# Teensy3_based_M_M_board_V4.net
KiCad netlist of a schematic drawn in EAGLE
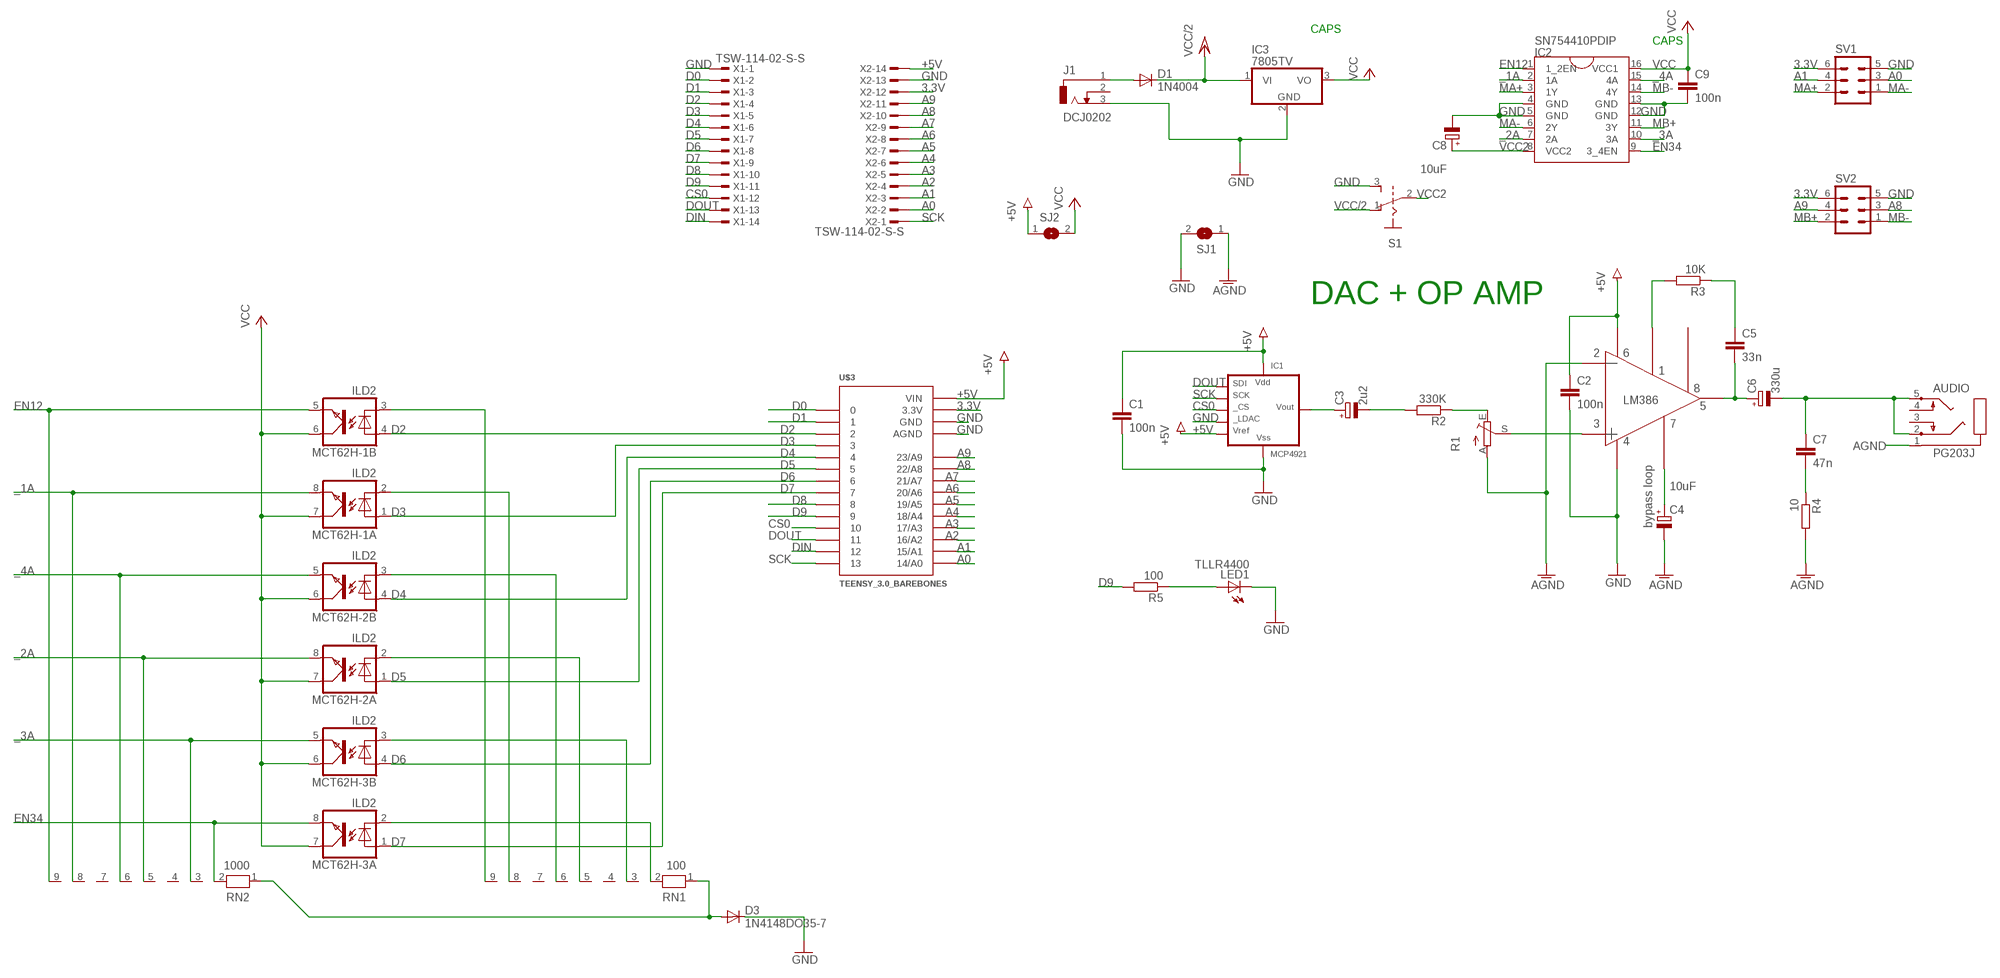
[diagram p0: schematic, sheet 1]

(export (version "E")
  (design (tool "Eeschema 10.0.6"))
  (components
    (comp (ref "AUDIO")
      (value "PG203J")
      (footprint "eagle-import:PG203J")
      (libsource (lib "eagle-import") (part "PG203J"))
    )
    (comp (ref "C1")
      (value "100n")
      (footprint "eagle-import:C050-030X075")
      (libsource (lib "eagle-import") (part "C-EU050-030X075"))
    )
    (comp (ref "C2")
      (value "100n")
      (footprint "eagle-import:C050-030X075")
      (libsource (lib "eagle-import") (part "C-EU050-030X075"))
    )
    (comp (ref "C3")
      (value "2u2")
      (footprint "eagle-import:E2-5")
      (libsource (lib "eagle-import") (part "CPOL-EUE2-5"))
    )
    (comp (ref "C4")
      (value "10uF")
      (footprint "eagle-import:E2-5")
      (libsource (lib "eagle-import") (part "CPOL-EUE2-5"))
    )
    (comp (ref "C5")
      (value "33n")
      (footprint "eagle-import:C050-030X075")
      (libsource (lib "eagle-import") (part "C-EU050-030X075"))
    )
    (comp (ref "C6")
      (value "330u")
      (footprint "eagle-import:E2,5-7")
      (libsource (lib "eagle-import") (part "CPOL-EUE2.5-7"))
    )
    (comp (ref "C7")
      (value "47n")
      (footprint "eagle-import:C050-030X075")
      (libsource (lib "eagle-import") (part "C-EU050-030X075"))
    )
    (comp (ref "C8")
      (value "10uF")
      (footprint "eagle-import:E2-5")
      (libsource (lib "eagle-import") (part "CPOL-EUE2-5"))
    )
    (comp (ref "C9")
      (value "100n")
      (footprint "eagle-import:C050-030X075")
      (libsource (lib "eagle-import") (part "C-EU050-030X075"))
    )
    (comp (ref "D1")
      (value "1N4004")
      (footprint "eagle-import:DO41-10")
      (libsource (lib "eagle-import") (part "1N4004"))
    )
    (comp (ref "D3")
      (value "1N4148DO35-7")
      (footprint "eagle-import:DO35-7")
      (libsource (lib "eagle-import") (part "1N4148DO35-7"))
    )
    (comp (ref "IC1")
      (value "MCP4921")
      (footprint "eagle-import:DIL8")
      (libsource (lib "eagle-import") (part "MCP4921P"))
    )
    (comp (ref "IC2")
      (value "SN754410PDIP")
      (footprint "eagle-import:DIL16")
      (libsource (lib "eagle-import") (part "SN754410PDIP"))
    )
    (comp (ref "IC3")
      (value "7805TV")
      (footprint "eagle-import:TO220V")
      (libsource (lib "eagle-import") (part "78TV05"))
    )
    (comp (ref "J1")
      (value "DCJ0202")
      (footprint "eagle-import:DCJ0202")
      (libsource (lib "eagle-import") (part "DCJ0202"))
    )
    (comp (ref "LED1")
      (value "TLLR4400")
      (footprint "eagle-import:LED3MM")
      (fields (field (name "MF") "VISHAY SEMICONDUCTOR"))
      (libsource (lib "eagle-import") (part "TLLR4400"))
    )
    (comp (ref "MCT62H-1")
      (value "ILD2")
      (footprint "eagle-import:DIL08")
      (libsource (lib "eagle-import") (part "ILD2"))
    )
    (comp (ref "MCT62H-2")
      (value "ILD2")
      (footprint "eagle-import:DIL08")
      (libsource (lib "eagle-import") (part "ILD2"))
    )
    (comp (ref "MCT62H-3")
      (value "ILD2")
      (footprint "eagle-import:DIL08")
      (libsource (lib "eagle-import") (part "ILD2"))
    )
    (comp (ref "R1")
      (value "TRIM_EU-CA9V")
      (footprint "eagle-import:CA9V")
      (libsource (lib "eagle-import") (part "TRIM_EU-CA9V"))
    )
    (comp (ref "R2")
      (value "330K")
      (footprint "eagle-import:0207_10")
      (libsource (lib "eagle-import") (part "R-EU_0207/10"))
    )
    (comp (ref "R3")
      (value "10K")
      (footprint "eagle-import:0207_10")
      (libsource (lib "eagle-import") (part "R-EU_0207/10"))
    )
    (comp (ref "R4")
      (value "10")
      (footprint "eagle-import:0207_10")
      (libsource (lib "eagle-import") (part "R-EU_0207/10"))
    )
    (comp (ref "R5")
      (value "100")
      (footprint "eagle-import:0207_10")
      (libsource (lib "eagle-import") (part "R-EU_0207/10"))
    )
    (comp (ref "RN1")
      (value "100")
      (footprint "eagle-import:RN-9")
      (libsource (lib "eagle-import") (part "RN08"))
    )
    (comp (ref "RN2")
      (value "1000")
      (footprint "eagle-import:RN-9")
      (libsource (lib "eagle-import") (part "RN08"))
    )
    (comp (ref "S1")
      (value "EG1218")
      (footprint "eagle-import:GF-126-0159")
      (libsource (lib "eagle-import") (part "EG1218"))
    )
    (comp (ref "SJ1") (value "SJ") (footprint "eagle-import:SJ") (libsource (lib "eagle-import") (part "SJ")))
    (comp (ref "SJ2") (value "SJ") (footprint "eagle-import:SJ") (libsource (lib "eagle-import") (part "SJ")))
    (comp (ref "SV1")
      (value "ML6")
      (footprint "eagle-import:ML6")
      (libsource (lib "eagle-import") (part "ML6"))
    )
    (comp (ref "SV2")
      (value "ML6")
      (footprint "eagle-import:ML6")
      (libsource (lib "eagle-import") (part "ML6"))
    )
    (comp (ref "U$2")
      (value "LM386")
      (footprint "eagle-import:LM386")
      (libsource (lib "eagle-import") (part "LM386OA"))
    )
    (comp (ref "U$3")
      (value "TEENSY_3.0_BAREBONES")
      (footprint "eagle-import:TEENSY_3.0_BAREBONES")
      (libsource (lib "eagle-import") (part "TEENSY_3.0_BAREBONES"))
    )
    (comp (ref "X1")
      (value "TSW-114-02-S-S")
      (footprint "eagle-import:TSW-114-02-S-S")
      (libsource (lib "eagle-import") (part "TSW-114-02-S-S"))
    )
    (comp (ref "X2")
      (value "TSW-114-02-S-S")
      (footprint "eagle-import:TSW-114-02-S-S")
      (libsource (lib "eagle-import") (part "TSW-114-02-S-S"))
    )
  )
  (nets
    (net (code "1") (name "+5V") (class "Default")
      (node (ref "C1") (pin "1") (pinfunction "1_1") (pintype "passive"))
      (node (ref "C2") (pin "1") (pinfunction "1_1") (pintype "passive"))
      (node (ref "IC1") (pin "1") (pinfunction "VDD_1") (pintype "power_in"))
      (node (ref "IC1") (pin "6") (pinfunction "VREF_6") (pintype "input"))
      (node (ref "SJ2") (pin "1") (pinfunction "1_1") (pintype "passive"))
      (node (ref "U$2") (pin "6") (pinfunction "P$6_6") (pintype "bidirectional"))
      (node (ref "U$3") (pin "VIN") (pinfunction "VIN_VIN") (pintype "power_in"))
      (node (ref "X2") (pin "14") (pinfunction "1_14") (pintype "passive"))
    )
    (net (code "2") (name "/3.3V") (class "Default")
      (node (ref "SV1") (pin "6") (pinfunction "6_6") (pintype "passive"))
      (node (ref "SV2") (pin "6") (pinfunction "6_6") (pintype "passive"))
      (node (ref "U$3") (pin "3.3V") (pinfunction "3.3V_3.3V") (pintype "power_in"))
      (node (ref "X2") (pin "12") (pinfunction "1_12") (pintype "passive"))
    )
    (net (code "3") (name "/A0") (class "Default")
      (node (ref "SV1") (pin "3") (pinfunction "3_3") (pintype "passive"))
      (node (ref "U$3") (pin "14/A0") (pinfunction "14/A0_14/A0") (pintype "bidirectional"))
      (node (ref "X2") (pin "2") (pinfunction "1_2") (pintype "passive"))
    )
    (net (code "4") (name "/A1") (class "Default")
      (node (ref "SV1") (pin "4") (pinfunction "4_4") (pintype "passive"))
      (node (ref "U$3") (pin "15/A1") (pinfunction "15/A1_15/A1") (pintype "bidirectional"))
      (node (ref "X2") (pin "3") (pinfunction "1_3") (pintype "passive"))
    )
    (net (code "5") (name "/A2") (class "Default")
      (node (ref "U$3") (pin "16/A2") (pinfunction "16/A2_16/A2") (pintype "bidirectional"))
      (node (ref "X2") (pin "4") (pinfunction "1_4") (pintype "passive"))
    )
    (net (code "6") (name "/A3") (class "Default")
      (node (ref "U$3") (pin "17/A3") (pinfunction "17/A3_17/A3") (pintype "bidirectional"))
      (node (ref "X2") (pin "5") (pinfunction "1_5") (pintype "passive"))
    )
    (net (code "7") (name "/A4") (class "Default")
      (node (ref "U$3") (pin "18/A4") (pinfunction "18/A4_18/A4") (pintype "bidirectional"))
      (node (ref "X2") (pin "6") (pinfunction "1_6") (pintype "passive"))
    )
    (net (code "8") (name "/A5") (class "Default")
      (node (ref "U$3") (pin "19/A5") (pinfunction "19/A5_19/A5") (pintype "bidirectional"))
      (node (ref "X2") (pin "7") (pinfunction "1_7") (pintype "passive"))
    )
    (net (code "9") (name "/A6") (class "Default")
      (node (ref "U$3") (pin "20/A6") (pinfunction "20/A6_20/A6") (pintype "bidirectional"))
      (node (ref "X2") (pin "8") (pinfunction "1_8") (pintype "passive"))
    )
    (net (code "10") (name "/A7") (class "Default")
      (node (ref "U$3") (pin "21/A7") (pinfunction "21/A7_21/A7") (pintype "bidirectional"))
      (node (ref "X2") (pin "9") (pinfunction "1_9") (pintype "passive"))
    )
    (net (code "11") (name "/A8") (class "Default")
      (node (ref "SV2") (pin "3") (pinfunction "3_3") (pintype "passive"))
      (node (ref "U$3") (pin "22/A8") (pinfunction "22/A8_22/A8") (pintype "bidirectional"))
      (node (ref "X2") (pin "10") (pinfunction "1_10") (pintype "passive"))
    )
    (net (code "12") (name "/A9") (class "Default")
      (node (ref "SV2") (pin "4") (pinfunction "4_4") (pintype "passive"))
      (node (ref "U$3") (pin "23/A9") (pinfunction "23/A9_23/A9") (pintype "bidirectional"))
      (node (ref "X2") (pin "11") (pinfunction "1_11") (pintype "passive"))
    )
    (net (code "13") (name "/CS0") (class "Default")
      (node (ref "IC1") (pin "2") (pinfunction "CS_2") (pintype "input"))
      (node (ref "U$3") (pin "10") (pinfunction "10_10") (pintype "bidirectional"))
      (node (ref "X1") (pin "12") (pinfunction "1_12") (pintype "passive"))
    )
    (net (code "14") (name "/D0") (class "Default")
      (node (ref "U$3") (pin "0") (pinfunction "0_0") (pintype "bidirectional"))
      (node (ref "X1") (pin "2") (pinfunction "1_2") (pintype "passive"))
    )
    (net (code "15") (name "/D1") (class "Default")
      (node (ref "U$3") (pin "1") (pinfunction "1_1") (pintype "bidirectional"))
      (node (ref "X1") (pin "3") (pinfunction "1_3") (pintype "passive"))
    )
    (net (code "16") (name "/D2") (class "Default")
      (node (ref "MCT62H-1") (pin "4") (pinfunction "A_4") (pintype "passive"))
      (node (ref "U$3") (pin "2") (pinfunction "2_2") (pintype "bidirectional"))
      (node (ref "X1") (pin "4") (pinfunction "1_4") (pintype "passive"))
    )
    (net (code "17") (name "/D3") (class "Default")
      (node (ref "MCT62H-1") (pin "1") (pinfunction "A_1") (pintype "passive"))
      (node (ref "U$3") (pin "3") (pinfunction "3_3") (pintype "bidirectional"))
      (node (ref "X1") (pin "5") (pinfunction "1_5") (pintype "passive"))
    )
    (net (code "18") (name "/D4") (class "Default")
      (node (ref "MCT62H-2") (pin "4") (pinfunction "A_4") (pintype "passive"))
      (node (ref "U$3") (pin "4") (pinfunction "4_4") (pintype "bidirectional"))
      (node (ref "X1") (pin "6") (pinfunction "1_6") (pintype "passive"))
    )
    (net (code "19") (name "/D5") (class "Default")
      (node (ref "MCT62H-2") (pin "1") (pinfunction "A_1") (pintype "passive"))
      (node (ref "U$3") (pin "5") (pinfunction "5_5") (pintype "bidirectional"))
      (node (ref "X1") (pin "7") (pinfunction "1_7") (pintype "passive"))
    )
    (net (code "20") (name "/D6") (class "Default")
      (node (ref "MCT62H-3") (pin "4") (pinfunction "A_4") (pintype "passive"))
      (node (ref "U$3") (pin "6") (pinfunction "6_6") (pintype "bidirectional"))
      (node (ref "X1") (pin "8") (pinfunction "1_8") (pintype "passive"))
    )
    (net (code "21") (name "/D7") (class "Default")
      (node (ref "MCT62H-3") (pin "1") (pinfunction "A_1") (pintype "passive"))
      (node (ref "U$3") (pin "7") (pinfunction "7_7") (pintype "bidirectional"))
      (node (ref "X1") (pin "9") (pinfunction "1_9") (pintype "passive"))
    )
    (net (code "22") (name "/D8") (class "Default")
      (node (ref "U$3") (pin "8") (pinfunction "8_8") (pintype "bidirectional"))
      (node (ref "X1") (pin "10") (pinfunction "1_10") (pintype "passive"))
    )
    (net (code "23") (name "/D9") (class "Default")
      (node (ref "R5") (pin "2") (pinfunction "2_2") (pintype "passive"))
      (node (ref "U$3") (pin "9") (pinfunction "9_9") (pintype "bidirectional"))
      (node (ref "X1") (pin "11") (pinfunction "1_11") (pintype "passive"))
    )
    (net (code "24") (name "/DIN") (class "Default")
      (node (ref "U$3") (pin "12") (pinfunction "12_12") (pintype "bidirectional"))
      (node (ref "X1") (pin "14") (pinfunction "1_14") (pintype "passive"))
    )
    (net (code "25") (name "/DOUT") (class "Default")
      (node (ref "IC1") (pin "4") (pinfunction "SDI_4") (pintype "input"))
      (node (ref "U$3") (pin "11") (pinfunction "11_11") (pintype "bidirectional"))
      (node (ref "X1") (pin "13") (pinfunction "1_13") (pintype "passive"))
    )
    (net (code "26") (name "/EN12") (class "Default")
      (node (ref "IC2") (pin "1") (pinfunction "1_2EN_1") (pintype "bidirectional"))
      (node (ref "MCT62H-1") (pin "5") (pinfunction "EMIT_5") (pintype "passive"))
      (node (ref "RN2") (pin "9") (pinfunction "9_9") (pintype "passive"))
    )
    (net (code "27") (name "/EN34") (class "Default")
      (node (ref "IC2") (pin "9") (pinfunction "3_4EN_9") (pintype "bidirectional"))
      (node (ref "MCT62H-3") (pin "8") (pinfunction "EMIT_8") (pintype "passive"))
      (node (ref "RN2") (pin "2") (pinfunction "2_2") (pintype "passive"))
    )
    (net (code "28") (name "/MA+") (class "Default")
      (node (ref "IC2") (pin "3") (pinfunction "1Y_3") (pintype "bidirectional"))
      (node (ref "SV1") (pin "2") (pinfunction "2_2") (pintype "passive"))
    )
    (net (code "29") (name "/MA-") (class "Default")
      (node (ref "IC2") (pin "6") (pinfunction "2Y_6") (pintype "bidirectional"))
      (node (ref "SV1") (pin "1") (pinfunction "1_1") (pintype "passive"))
    )
    (net (code "30") (name "/MB+") (class "Default")
      (node (ref "IC2") (pin "11") (pinfunction "3Y_11") (pintype "bidirectional"))
      (node (ref "SV2") (pin "2") (pinfunction "2_2") (pintype "passive"))
    )
    (net (code "31") (name "/MB-") (class "Default")
      (node (ref "IC2") (pin "14") (pinfunction "4Y_14") (pintype "bidirectional"))
      (node (ref "SV2") (pin "1") (pinfunction "1_1") (pintype "passive"))
    )
    (net (code "32") (name "/SCK") (class "Default")
      (node (ref "IC1") (pin "3") (pinfunction "SCK_3") (pintype "input"))
      (node (ref "U$3") (pin "13") (pinfunction "13_13") (pintype "bidirectional"))
      (node (ref "X2") (pin "1") (pinfunction "1_1") (pintype "passive"))
    )
    (net (code "33") (name "/VCC2") (class "Default")
      (node (ref "C8") (pin "+") (pinfunction "+_+") (pintype "passive"))
      (node (ref "IC2") (pin "8") (pinfunction "VCC2_8") (pintype "bidirectional"))
      (node (ref "S1") (pin "2") (pinfunction "02_2") (pintype "passive"))
    )
    (net (code "34") (name "/_1A") (class "Default")
      (node (ref "IC2") (pin "2") (pinfunction "1A_2") (pintype "bidirectional"))
      (node (ref "MCT62H-1") (pin "8") (pinfunction "EMIT_8") (pintype "passive"))
      (node (ref "RN2") (pin "8") (pinfunction "8_8") (pintype "passive"))
    )
    (net (code "35") (name "/_2A") (class "Default")
      (node (ref "IC2") (pin "7") (pinfunction "2A_7") (pintype "bidirectional"))
      (node (ref "MCT62H-2") (pin "8") (pinfunction "EMIT_8") (pintype "passive"))
      (node (ref "RN2") (pin "5") (pinfunction "5_5") (pintype "passive"))
    )
    (net (code "36") (name "/_3A") (class "Default")
      (node (ref "IC2") (pin "10") (pinfunction "3A_10") (pintype "bidirectional"))
      (node (ref "MCT62H-3") (pin "5") (pinfunction "EMIT_5") (pintype "passive"))
      (node (ref "RN2") (pin "3") (pinfunction "3_3") (pintype "passive"))
    )
    (net (code "37") (name "/_4A") (class "Default")
      (node (ref "IC2") (pin "15") (pinfunction "4A_15") (pintype "bidirectional"))
      (node (ref "MCT62H-2") (pin "5") (pinfunction "EMIT_5") (pintype "passive"))
      (node (ref "RN2") (pin "6") (pinfunction "6_6") (pintype "passive"))
    )
    (net (code "38") (name "AGND") (class "Default")
      (node (ref "AUDIO") (pin "1") (pinfunction "1_1") (pintype "passive"))
      (node (ref "C4") (pin "-") (pinfunction "-_-") (pintype "passive"))
      (node (ref "R1") (pin "A") (pinfunction "A_A") (pintype "passive"))
      (node (ref "R4") (pin "2") (pinfunction "2_2") (pintype "passive"))
      (node (ref "SJ1") (pin "1") (pinfunction "1_1") (pintype "passive"))
      (node (ref "U$2") (pin "2") (pinfunction "P$2_2") (pintype "bidirectional"))
    )
    (net (code "39") (name "GND") (class "Default")
      (node (ref "C1") (pin "2") (pinfunction "2_2") (pintype "passive"))
      (node (ref "C2") (pin "2") (pinfunction "2_2") (pintype "passive"))
      (node (ref "C8") (pin "-") (pinfunction "-_-") (pintype "passive"))
      (node (ref "C9") (pin "2") (pinfunction "2_2") (pintype "passive"))
      (node (ref "D3") (pin "C") (pinfunction "C_C") (pintype "passive"))
      (node (ref "IC1") (pin "5") (pinfunction "LDAC_5") (pintype "input"))
      (node (ref "IC1") (pin "7") (pinfunction "VSS_7") (pintype "power_in"))
      (node (ref "IC2") (pin "12") (pinfunction "GND_12") (pintype "bidirectional"))
      (node (ref "IC2") (pin "13") (pinfunction "GND_13") (pintype "bidirectional"))
      (node (ref "IC2") (pin "4") (pinfunction "GND_4") (pintype "bidirectional"))
      (node (ref "IC2") (pin "5") (pinfunction "GND_5") (pintype "bidirectional"))
      (node (ref "IC3") (pin "2") (pinfunction "GND_2") (pintype "passive"))
      (node (ref "J1") (pin "3") (pinfunction "3_3") (pintype "passive"))
      (node (ref "LED1") (pin "K") (pinfunction "C_K") (pintype "passive"))
      (node (ref "S1") (pin "3") (pinfunction "3_3") (pintype "passive"))
      (node (ref "SJ1") (pin "2") (pinfunction "2_2") (pintype "passive"))
      (node (ref "SV1") (pin "5") (pinfunction "5_5") (pintype "passive"))
      (node (ref "SV2") (pin "5") (pinfunction "5_5") (pintype "passive"))
      (node (ref "U$2") (pin "4") (pinfunction "P$4_4") (pintype "bidirectional"))
      (node (ref "U$3") (pin "AGND") (pinfunction "AGND_AGND") (pintype "power_in"))
      (node (ref "U$3") (pin "GND") (pinfunction "GND_GND") (pintype "power_in"))
      (node (ref "X1") (pin "1") (pinfunction "1_1") (pintype "passive"))
      (node (ref "X2") (pin "13") (pinfunction "1_13") (pintype "passive"))
    )
    (net (code "40") (name "Net-(AUDIO-Pad2)") (class "Default")
      (node (ref "AUDIO") (pin "2") (pinfunction "2_2") (pintype "passive"))
      (node (ref "AUDIO") (pin "5") (pinfunction "5_5") (pintype "passive"))
      (node (ref "C6") (pin "-") (pinfunction "-_-") (pintype "passive"))
      (node (ref "C7") (pin "1") (pinfunction "1_1") (pintype "passive"))
    )
    (net (code "41") (name "Net-(C3-Pad-)") (class "Default")
      (node (ref "C3") (pin "-") (pinfunction "-_-") (pintype "passive"))
      (node (ref "R2") (pin "2") (pinfunction "2_2") (pintype "passive"))
    )
    (net (code "42") (name "Net-(C5-Pad1)") (class "Default")
      (node (ref "C5") (pin "1") (pinfunction "1_1") (pintype "passive"))
      (node (ref "R3") (pin "1") (pinfunction "1_1") (pintype "passive"))
    )
    (net (code "43") (name "Net-(C7-Pad2)") (class "Default")
      (node (ref "C7") (pin "2") (pinfunction "2_2") (pintype "passive"))
      (node (ref "R4") (pin "1") (pinfunction "1_1") (pintype "passive"))
    )
    (net (code "44") (name "Net-(D1-PadA)") (class "Default")
      (node (ref "D1") (pin "A") (pinfunction "A_A") (pintype "passive"))
      (node (ref "J1") (pin "1") (pinfunction "1_1") (pintype "passive"))
    )
    (net (code "45") (name "Net-(D3-PadA)") (class "Default")
      (node (ref "D3") (pin "A") (pinfunction "A_A") (pintype "passive"))
      (node (ref "RN1") (pin "1") (pinfunction "1_1") (pintype "passive"))
      (node (ref "RN2") (pin "1") (pinfunction "1_1") (pintype "passive"))
    )
    (net (code "46") (name "Net-(IC1-VOUT)") (class "Default")
      (node (ref "C3") (pin "+") (pinfunction "+_+") (pintype "passive"))
      (node (ref "IC1") (pin "8") (pinfunction "VOUT_8") (pintype "output"))
    )
    (net (code "47") (name "Net-(LED1-PadA)") (class "Default")
      (node (ref "LED1") (pin "A") (pinfunction "A_A") (pintype "passive"))
      (node (ref "R5") (pin "1") (pinfunction "1_1") (pintype "passive"))
    )
    (net (code "48") (name "Net-(MCT62H-1A-C)") (class "Default")
      (node (ref "MCT62H-1") (pin "2") (pinfunction "C_2") (pintype "passive"))
      (node (ref "RN1") (pin "8") (pinfunction "8_8") (pintype "passive"))
    )
    (net (code "49") (name "Net-(MCT62H-1B-C)") (class "Default")
      (node (ref "MCT62H-1") (pin "3") (pinfunction "C_3") (pintype "passive"))
      (node (ref "RN1") (pin "9") (pinfunction "9_9") (pintype "passive"))
    )
    (net (code "50") (name "Net-(MCT62H-2A-C)") (class "Default")
      (node (ref "MCT62H-2") (pin "2") (pinfunction "C_2") (pintype "passive"))
      (node (ref "RN1") (pin "5") (pinfunction "5_5") (pintype "passive"))
    )
    (net (code "51") (name "Net-(MCT62H-2B-C)") (class "Default")
      (node (ref "MCT62H-2") (pin "3") (pinfunction "C_3") (pintype "passive"))
      (node (ref "RN1") (pin "6") (pinfunction "6_6") (pintype "passive"))
    )
    (net (code "52") (name "Net-(MCT62H-3A-C)") (class "Default")
      (node (ref "MCT62H-3") (pin "2") (pinfunction "C_2") (pintype "passive"))
      (node (ref "RN1") (pin "2") (pinfunction "2_2") (pintype "passive"))
    )
    (net (code "53") (name "Net-(MCT62H-3B-C)") (class "Default")
      (node (ref "MCT62H-3") (pin "3") (pinfunction "C_3") (pintype "passive"))
      (node (ref "RN1") (pin "3") (pinfunction "3_3") (pintype "passive"))
    )
    (net (code "54") (name "Net-(R1-PadE)") (class "Default")
      (node (ref "R1") (pin "E") (pinfunction "E_E") (pintype "passive"))
      (node (ref "R2") (pin "1") (pinfunction "1_1") (pintype "passive"))
    )
    (net (code "55") (name "Net-(U$2-P$1)") (class "Default")
      (node (ref "R3") (pin "2") (pinfunction "2_2") (pintype "passive"))
      (node (ref "U$2") (pin "1") (pinfunction "P$1_1") (pintype "bidirectional"))
    )
    (net (code "56") (name "Net-(U$2-P$3)") (class "Default")
      (node (ref "R1") (pin "S") (pinfunction "S_S") (pintype "passive"))
      (node (ref "U$2") (pin "3") (pinfunction "P$3_3") (pintype "bidirectional"))
    )
    (net (code "57") (name "Net-(U$2-P$5)") (class "Default")
      (node (ref "C5") (pin "2") (pinfunction "2_2") (pintype "passive"))
      (node (ref "C6") (pin "+") (pinfunction "+_+") (pintype "passive"))
      (node (ref "U$2") (pin "5") (pinfunction "P$5_5") (pintype "bidirectional"))
    )
    (net (code "58") (name "Net-(U$2-P$7)") (class "Default")
      (node (ref "C4") (pin "+") (pinfunction "+_+") (pintype "passive"))
      (node (ref "U$2") (pin "7") (pinfunction "P$7_7") (pintype "bidirectional"))
    )
    (net (code "59") (name "VCC") (class "Default")
      (node (ref "C9") (pin "1") (pinfunction "1_1") (pintype "passive"))
      (node (ref "IC2") (pin "16") (pinfunction "VCC1_16") (pintype "bidirectional"))
      (node (ref "IC3") (pin "3") (pinfunction "VO_3") (pintype "passive"))
      (node (ref "MCT62H-1") (pin "6") (pinfunction "COL_6") (pintype "passive"))
      (node (ref "MCT62H-1") (pin "7") (pinfunction "COL_7") (pintype "passive"))
      (node (ref "MCT62H-2") (pin "6") (pinfunction "COL_6") (pintype "passive"))
      (node (ref "MCT62H-2") (pin "7") (pinfunction "COL_7") (pintype "passive"))
      (node (ref "MCT62H-3") (pin "6") (pinfunction "COL_6") (pintype "passive"))
      (node (ref "MCT62H-3") (pin "7") (pinfunction "COL_7") (pintype "passive"))
      (node (ref "SJ2") (pin "2") (pinfunction "2_2") (pintype "passive"))
    )
    (net (code "60") (name "VCC{slash}2") (class "Default")
      (node (ref "D1") (pin "C") (pinfunction "C_C") (pintype "passive"))
      (node (ref "IC3") (pin "1") (pinfunction "VI_1") (pintype "input"))
      (node (ref "S1") (pin "1") (pinfunction "1_1") (pintype "passive"))
    )
    (net (code "61") (name "unconnected-(AUDIO-Pad3)") (class "Default")
      (node (ref "AUDIO") (pin "3") (pinfunction "3_3") (pintype "passive"))
    )
    (net (code "62") (name "unconnected-(AUDIO-Pad4)") (class "Default")
      (node (ref "AUDIO") (pin "4") (pinfunction "4_4") (pintype "passive"))
    )
    (net (code "63") (name "unconnected-(J1-Pad2)") (class "Default")
      (node (ref "J1") (pin "2") (pinfunction "2_2") (pintype "passive"))
    )
    (net (code "64") (name "unconnected-(RN1-Pad4)") (class "Default")
      (node (ref "RN1") (pin "4") (pinfunction "4_4") (pintype "passive"))
    )
    (net (code "65") (name "unconnected-(RN1-Pad7)") (class "Default")
      (node (ref "RN1") (pin "7") (pinfunction "7_7") (pintype "passive"))
    )
    (net (code "66") (name "unconnected-(RN2-Pad4)") (class "Default")
      (node (ref "RN2") (pin "4") (pinfunction "4_4") (pintype "passive"))
    )
    (net (code "67") (name "unconnected-(RN2-Pad7)") (class "Default")
      (node (ref "RN2") (pin "7") (pinfunction "7_7") (pintype "passive"))
    )
    (net (code "68") (name "unconnected-(U$2-P$8-Pad8)") (class "Default")
      (node (ref "U$2") (pin "8") (pinfunction "P$8_8") (pintype "bidirectional"))
    )
  )
)
